# wheatstone.net
KiCad netlist of a schematic drawn in EAGLE
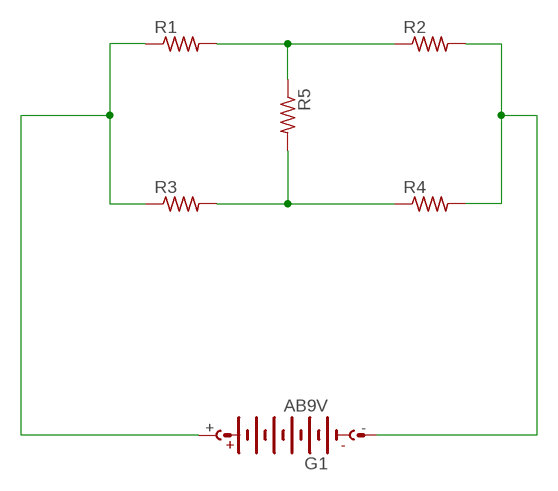
[diagram p0: schematic, sheet 1]

(export (version "E")
  (design (tool "Eeschema 10.0.6"))
  (components
    (comp (ref "G1")
      (value "AB9V")
      (footprint "eagle-import:AB9V")
      (libsource (lib "eagle-import") (part "AB9V"))
    )
    (comp (ref "R1")
      (value "R-US_R0603")
      (footprint "eagle-import:R0603")
      (libsource (lib "eagle-import") (part "R-US_R0603"))
    )
    (comp (ref "R2")
      (value "R-US_R0603")
      (footprint "eagle-import:R0603")
      (libsource (lib "eagle-import") (part "R-US_R0603"))
    )
    (comp (ref "R3")
      (value "R-US_R0603")
      (footprint "eagle-import:R0603")
      (libsource (lib "eagle-import") (part "R-US_R0603"))
    )
    (comp (ref "R4")
      (value "R-US_R0603")
      (footprint "eagle-import:R0603")
      (libsource (lib "eagle-import") (part "R-US_R0603"))
    )
    (comp (ref "R5")
      (value "R-US_R0603")
      (footprint "eagle-import:R0603")
      (libsource (lib "eagle-import") (part "R-US_R0603"))
    )
  )
  (nets
    (net (code "1") (name "Net-(G1-Pad+)") (class "Default")
      (node (ref "G1") (pin "+") (pinfunction "+_+") (pintype "passive"))
      (node (ref "R1") (pin "1") (pinfunction "1_1") (pintype "passive"))
      (node (ref "R3") (pin "1") (pinfunction "1_1") (pintype "passive"))
    )
    (net (code "2") (name "Net-(G1-Pad-)") (class "Default")
      (node (ref "G1") (pin "-") (pinfunction "-_-") (pintype "passive"))
      (node (ref "R2") (pin "2") (pinfunction "2_2") (pintype "passive"))
      (node (ref "R4") (pin "2") (pinfunction "2_2") (pintype "passive"))
    )
    (net (code "3") (name "Net-(R1-Pad2)") (class "Default")
      (node (ref "R1") (pin "2") (pinfunction "2_2") (pintype "passive"))
      (node (ref "R2") (pin "1") (pinfunction "1_1") (pintype "passive"))
      (node (ref "R5") (pin "1") (pinfunction "1_1") (pintype "passive"))
    )
    (net (code "4") (name "Net-(R3-Pad2)") (class "Default")
      (node (ref "R3") (pin "2") (pinfunction "2_2") (pintype "passive"))
      (node (ref "R4") (pin "1") (pinfunction "1_1") (pintype "passive"))
      (node (ref "R5") (pin "2") (pinfunction "2_2") (pintype "passive"))
    )
  )
)
